# Un_SecUSB.net
KiCad netlist of a schematic drawn in EAGLE
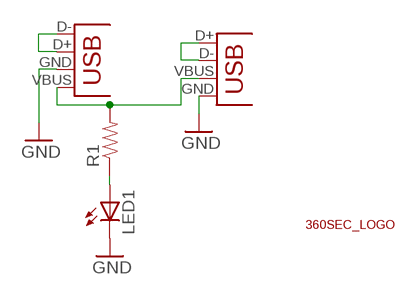
[diagram p0: schematic, sheet 1]

(export (version "E")
  (design (tool "Eeschema 10.0.6"))
  (components
    (comp (ref "LED1")
      (value "LED0603")
      (footprint "eagle-import:LED-0603")
      (libsource (lib "eagle-import") (part "LED0603"))
    )
    (comp (ref "R1")
      (value "RESISTOR0603-RES")
      (footprint "eagle-import:0603-RES")
      (libsource (lib "eagle-import") (part "RESISTOR0603-RES"))
    )
    (comp (ref "U$3")
      (value "360SEC_LOGO_0.8")
      (footprint "eagle-import:360SEC_0.8")
      (libsource (lib "eagle-import") (part "360SEC_LOGO_0.8"))
    )
    (comp (ref "X1")
      (value "USB_4-A-H")
      (footprint "eagle-import:USB-A-H")
      (libsource (lib "eagle-import") (part "USB_4-A-H"))
    )
    (comp (ref "X2")
      (value "USB_4_1")
      (footprint "eagle-import:USB-A-1")
      (libsource (lib "eagle-import") (part "USB_4_1"))
    )
  )
  (nets
    (net (code "1") (name "GND") (class "Default")
      (node (ref "LED1") (pin "C") (pinfunction "C_C") (pintype "passive"))
      (node (ref "X1") (pin "GND") (pinfunction "VBUS_GND") (pintype "bidirectional"))
      (node (ref "X2") (pin "GND") (pinfunction "GND_GND") (pintype "bidirectional"))
    )
    (net (code "2") (name "Net-(LED1-PadA)") (class "Default")
      (node (ref "LED1") (pin "A") (pinfunction "A_A") (pintype "passive"))
      (node (ref "R1") (pin "1") (pinfunction "1_1") (pintype "passive"))
    )
    (net (code "3") (name "Net-(X1-D+)") (class "Default")
      (node (ref "X1") (pin "D+") (pinfunction "D-_D+") (pintype "bidirectional"))
      (node (ref "X1") (pin "D-") (pinfunction "D+_D-") (pintype "bidirectional"))
    )
    (net (code "4") (name "Net-(X1-GND)") (class "Default")
      (node (ref "R1") (pin "2") (pinfunction "2_2") (pintype "passive"))
      (node (ref "X1") (pin "VBUS") (pinfunction "GND_VBUS") (pintype "bidirectional"))
      (node (ref "X2") (pin "VBUS") (pinfunction "VBUS_VBUS") (pintype "bidirectional"))
    )
    (net (code "5") (name "Net-(X2-PadD+)") (class "Default")
      (node (ref "X2") (pin "D+") (pinfunction "D+_D+") (pintype "bidirectional"))
      (node (ref "X2") (pin "D-") (pinfunction "D-_D-") (pintype "bidirectional"))
    )
  )
)
